# Dart_Controller_SCH.net
KiCad netlist of a schematic drawn in Altium Designer
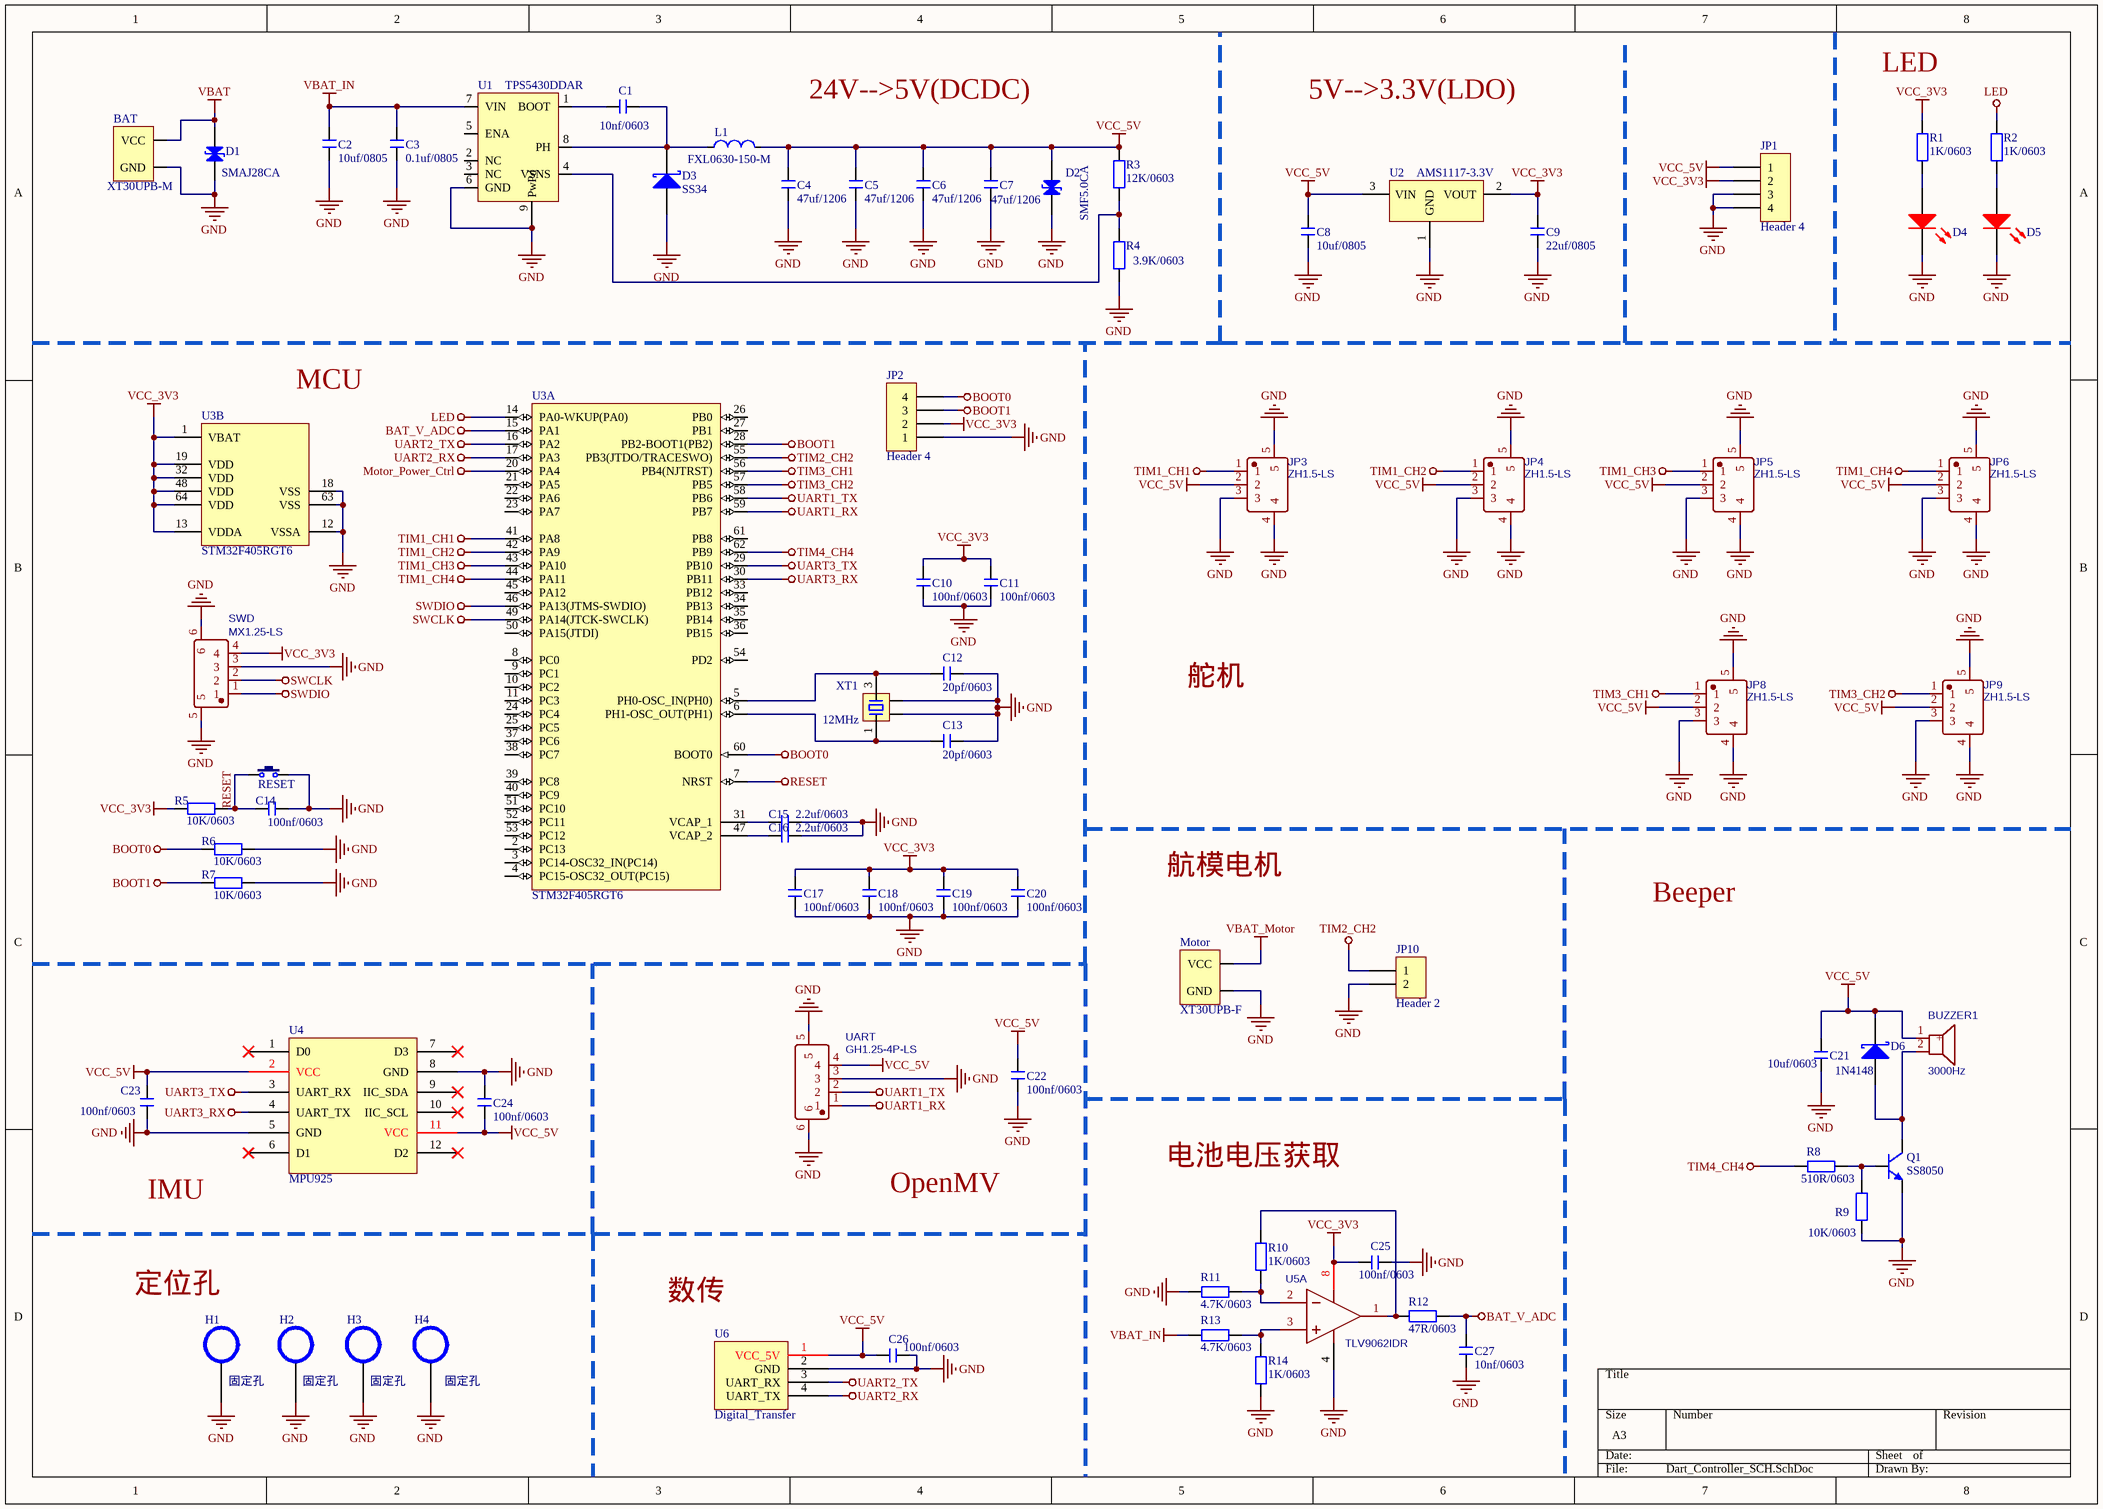
[diagram p0: Dart_Controller_SCH.SchDoc]

(export (version "E")
  (design (tool "Eeschema 10.0.6"))
  (components
    (comp (ref "BAT")
      (value "XT30UPB-M")
      (footprint "XT30UPB-M")
      (description "公头(立式)")
      (libsource (lib "Dart_Controller_Schlib") (part "XT30UPB-M"))
    )
    (comp (ref "BUZZER1")
      (value "3000Hz")
      (footprint "BUZ-TH_BD9.6-P5.00-D0.7-FD")
      (description "蜂鸣器")
      (fields (field (name "MANUFACTURER") "华能") (field (name "MANUFACTURER PART") "HNB09A05"))
      (libsource (lib "Dart_Controller_Schlib") (part "3000Hz"))
    )
    (comp (ref "C1")
      (value "10nf/0603")
      (footprint "C 0603_M")
      (description "贴片电容")
      (libsource (lib "Dart_Controller_Schlib") (part "C 0603"))
    )
    (comp (ref "C2")
      (value "10uf/0805")
      (footprint "C 0805_M")
      (description "贴片电容")
      (libsource (lib "Dart_Controller_Schlib") (part "C 0805"))
    )
    (comp (ref "C3")
      (value "0.1uf/0805")
      (footprint "C 0805_M")
      (description "贴片电容")
      (libsource (lib "Dart_Controller_Schlib") (part "C 0805"))
    )
    (comp (ref "C4")
      (value "47uf/1206")
      (footprint "C 1206_M")
      (description "贴片电容")
      (libsource (lib "Dart_Controller_Schlib") (part "C 1206"))
    )
    (comp (ref "C5")
      (value "47uf/1206")
      (footprint "C 1206_M")
      (description "贴片电容")
      (libsource (lib "Dart_Controller_Schlib") (part "C 1206"))
    )
    (comp (ref "C6")
      (value "47uf/1206")
      (footprint "C 1206_M")
      (description "贴片电容")
      (libsource (lib "Dart_Controller_Schlib") (part "C 1206"))
    )
    (comp (ref "C7")
      (value "47uf/1206")
      (footprint "C 1206_M")
      (description "贴片电容")
      (libsource (lib "Dart_Controller_Schlib") (part "C 1206"))
    )
    (comp (ref "C8")
      (value "10uf/0805")
      (footprint "C 0805_M")
      (description "贴片电容")
      (libsource (lib "Dart_Controller_Schlib") (part "C 0805"))
    )
    (comp (ref "C9")
      (value "22uf/0805")
      (footprint "C 0805_M")
      (description "贴片电容")
      (libsource (lib "Dart_Controller_Schlib") (part "C 0805"))
    )
    (comp (ref "C10")
      (value "100nf/0603")
      (footprint "C 0603_M")
      (description "贴片电容")
      (libsource (lib "Dart_Controller_Schlib") (part "C 0603"))
    )
    (comp (ref "C11")
      (value "100nf/0603")
      (footprint "C 0603_M")
      (description "贴片电容")
      (libsource (lib "Dart_Controller_Schlib") (part "C 0603"))
    )
    (comp (ref "C12")
      (value "20pf/0603")
      (footprint "C 0603_M")
      (description "贴片电容")
      (libsource (lib "Dart_Controller_Schlib") (part "C 0603"))
    )
    (comp (ref "C13")
      (value "20pf/0603")
      (footprint "C 0603_M")
      (description "贴片电容")
      (libsource (lib "Dart_Controller_Schlib") (part "C 0603"))
    )
    (comp (ref "C14")
      (value "100nf/0603")
      (footprint "C 0603_M")
      (description "贴片电容")
      (libsource (lib "Dart_Controller_Schlib") (part "C 0603"))
    )
    (comp (ref "C15")
      (value "2.2uf/0603")
      (footprint "C 0603_M")
      (description "贴片电容")
      (libsource (lib "Dart_Controller_Schlib") (part "C 0603"))
    )
    (comp (ref "C16")
      (value "2.2uf/0603")
      (footprint "C 0603_M")
      (description "贴片电容")
      (libsource (lib "Dart_Controller_Schlib") (part "C 0603"))
    )
    (comp (ref "C17")
      (value "100nf/0603")
      (footprint "C 0603_M")
      (description "贴片电容")
      (libsource (lib "Dart_Controller_Schlib") (part "C 0603"))
    )
    (comp (ref "C18")
      (value "100nf/0603")
      (footprint "C 0603_M")
      (description "贴片电容")
      (libsource (lib "Dart_Controller_Schlib") (part "C 0603"))
    )
    (comp (ref "C19")
      (value "100nf/0603")
      (footprint "C 0603_M")
      (description "贴片电容")
      (libsource (lib "Dart_Controller_Schlib") (part "C 0603"))
    )
    (comp (ref "C20")
      (value "100nf/0603")
      (footprint "C 0603_M")
      (description "贴片电容")
      (libsource (lib "Dart_Controller_Schlib") (part "C 0603"))
    )
    (comp (ref "C21")
      (value "10uf/0603")
      (footprint "C 0603_M")
      (description "贴片电容")
      (libsource (lib "Dart_Controller_Schlib") (part "C 0603"))
    )
    (comp (ref "C22")
      (value "100nf/0603")
      (footprint "C 0603_M")
      (description "贴片电容")
      (libsource (lib "Dart_Controller_Schlib") (part "C 0603"))
    )
    (comp (ref "C23")
      (value "100nf/0603")
      (footprint "C 0603_M")
      (description "贴片电容")
      (libsource (lib "Dart_Controller_Schlib") (part "C 0603"))
    )
    (comp (ref "C24")
      (value "100nf/0603")
      (footprint "C 0603_M")
      (description "贴片电容")
      (libsource (lib "Dart_Controller_Schlib") (part "C 0603"))
    )
    (comp (ref "C25")
      (value "100nf/0603")
      (footprint "C 0603_M")
      (description "贴片电容")
      (libsource (lib "Cap_Mananger_Schlib") (part "C 0603"))
    )
    (comp (ref "C26")
      (value "100nf/0603")
      (footprint "C 0603_M")
      (description "贴片电容")
      (libsource (lib "Dart_Controller_Schlib") (part "C 0603"))
    )
    (comp (ref "C27")
      (value "10nf/0603")
      (footprint "C 0603_M")
      (description "贴片电容")
      (libsource (lib "Cap_Mananger_Schlib") (part "C 0603"))
    )
    (comp (ref "D1")
      (value "SMAJ28CA")
      (footprint "SMA")
      (description "双向瞬态电压抑制二极管")
      (libsource (lib "Dart_Controller_Schlib") (part "SMAJ28CA"))
    )
    (comp (ref "D2")
      (value "SMF5.0CA")
      (footprint "SOD-123FL_L2.8-W1.8-LS3.7-BI")
      (description "双向瞬态电压抑制二极管")
      (libsource (lib "Dart_Controller_Schlib") (part "SMF5.0CA"))
    )
    (comp (ref "D3")
      (value "SS34")
      (footprint "SMA")
      (description "肖特基二极管")
      (libsource (lib "Dart_Controller_Schlib") (part "SS34"))
    )
    (comp (ref "D4")
      (value "LED")
      (footprint "LED0603-RD_RED")
      (description "发光二极管")
      (fields (field (name "PUBLISHER") "Altium Limited"))
      (libsource (lib "Dart_Controller_Schlib") (part "LED_R"))
    )
    (comp (ref "D5")
      (value "LED")
      (footprint "LED0603-RD_RED")
      (description "发光二极管")
      (fields (field (name "PUBLISHER") "Altium Limited"))
      (libsource (lib "Dart_Controller_Schlib") (part "LED_R"))
    )
    (comp (ref "D6")
      (value "1N4148")
      (footprint "SOD-323_L1.8-W1.3-LS2.5-RD")
      (description "开关二极管")
      (libsource (lib "Dart_Controller_Schlib") (part "1N4148WS"))
    )
    (comp (ref "H1") (value "固定孔") (footprint "铜柱孔") (libsource (lib "Dart_Controller_Schlib") (part "铜柱孔")))
    (comp (ref "H2") (value "固定孔") (footprint "铜柱孔") (libsource (lib "Dart_Controller_Schlib") (part "铜柱孔")))
    (comp (ref "H3") (value "固定孔") (footprint "铜柱孔") (libsource (lib "Dart_Controller_Schlib") (part "铜柱孔")))
    (comp (ref "H4") (value "固定孔") (footprint "铜柱孔") (libsource (lib "Dart_Controller_Schlib") (part "铜柱孔")))
    (comp (ref "JP1")
      (value "Header 4")
      (footprint "HDR2.54-LI-4P")
      (description "Header, 4-Pin")
      (fields (field (name "PUBLISHER") "Altium Limited"))
      (libsource (lib "Dart_Controller_Schlib") (part "Header 4"))
    )
    (comp (ref "JP2")
      (value "Header 4")
      (footprint "HDR2.54-LI-4P")
      (description "Header, 4-Pin")
      (fields (field (name "PUBLISHER") "Altium Limited"))
      (libsource (lib "") (part "Header 4_1"))
    )
    (comp (ref "JP3")
      (value "ZH1.5-LS")
      (footprint "ZH1.5")
      (fields
        (field (name "MANUFACTURER") "HCTL(华灿天禄)")
        (field (name "MANUFACTURER PART") "HC-ZH-3PLT")
        (field (name "CONTRIBUTOR") "LCSC")
      )
      (libsource (lib "Dart_Controller_Schlib") (part "ZH1.5-LS"))
    )
    (comp (ref "JP4")
      (value "ZH1.5-LS")
      (footprint "ZH1.5")
      (fields
        (field (name "MANUFACTURER") "HCTL(华灿天禄)")
        (field (name "MANUFACTURER PART") "HC-ZH-3PLT")
        (field (name "CONTRIBUTOR") "LCSC")
      )
      (libsource (lib "Dart_Controller_Schlib") (part "ZH1.5-LS"))
    )
    (comp (ref "JP5")
      (value "ZH1.5-LS")
      (footprint "ZH1.5")
      (fields
        (field (name "MANUFACTURER") "HCTL(华灿天禄)")
        (field (name "MANUFACTURER PART") "HC-ZH-3PLT")
        (field (name "CONTRIBUTOR") "LCSC")
      )
      (libsource (lib "Dart_Controller_Schlib") (part "ZH1.5-LS"))
    )
    (comp (ref "JP6")
      (value "ZH1.5-LS")
      (footprint "ZH1.5")
      (fields
        (field (name "MANUFACTURER") "HCTL(华灿天禄)")
        (field (name "MANUFACTURER PART") "HC-ZH-3PLT")
        (field (name "CONTRIBUTOR") "LCSC")
      )
      (libsource (lib "Dart_Controller_Schlib") (part "ZH1.5-LS"))
    )
    (comp (ref "JP8")
      (value "ZH1.5-LS")
      (footprint "ZH1.5")
      (fields
        (field (name "MANUFACTURER") "HCTL(华灿天禄)")
        (field (name "MANUFACTURER PART") "HC-ZH-3PLT")
        (field (name "CONTRIBUTOR") "LCSC")
      )
      (libsource (lib "Dart_Controller_Schlib") (part "ZH1.5-LS"))
    )
    (comp (ref "JP9")
      (value "ZH1.5-LS")
      (footprint "ZH1.5")
      (fields
        (field (name "MANUFACTURER") "HCTL(华灿天禄)")
        (field (name "MANUFACTURER PART") "HC-ZH-3PLT")
        (field (name "CONTRIBUTOR") "LCSC")
      )
      (libsource (lib "Dart_Controller_Schlib") (part "ZH1.5-LS"))
    )
    (comp (ref "JP10")
      (value "Header 2")
      (footprint "HDR2.54-LI-2P")
      (description "Header, 2-Pin")
      (fields (field (name "PUBLISHER") "Altium Limited"))
      (libsource (lib "Dart_Controller_Schlib") (part "Header 2"))
    )
    (comp (ref "L1")
      (value "FXL0630-150-M")
      (footprint "L-SMD-0630")
      (description "功率电感")
      (libsource (lib "Dart_Controller_Schlib") (part "FXL0630-150-M"))
    )
    (comp (ref "Motor")
      (value "XT30UPB-F")
      (footprint "XT30UPB-F")
      (description "母头(立式)")
      (libsource (lib "Dart_Controller_Schlib") (part "XT30UPB-F"))
    )
    (comp (ref "Q1")
      (value "SS8050")
      (footprint "SOT23-3L")
      (description "高频放大-NPN型")
      (fields (field (name "版权归属") "封装库来自淘宝 ID：黄晶宝石"))
      (libsource (lib "Dart_Controller_Schlib") (part "SS8050-SMD"))
    )
    (comp (ref "R1")
      (value "1K/0603")
      (footprint "R 0603_M")
      (description "贴片电阻")
      (fields (field (name "版权归属") "来自淘宝 ID：黄晶宝石"))
      (libsource (lib "Dart_Controller_Schlib") (part "R 0603"))
    )
    (comp (ref "R2")
      (value "1K/0603")
      (footprint "R 0603_M")
      (description "贴片电阻")
      (fields (field (name "版权归属") "来自淘宝 ID：黄晶宝石"))
      (libsource (lib "Dart_Controller_Schlib") (part "R 0603"))
    )
    (comp (ref "R3")
      (value "12K/0603")
      (footprint "R 0603_M")
      (description "贴片电阻")
      (fields (field (name "版权归属") "来自淘宝 ID：黄晶宝石"))
      (libsource (lib "Dart_Controller_Schlib") (part "R 0603"))
    )
    (comp (ref "R4")
      (value "3.9K/0603")
      (footprint "R 0603_M")
      (description "贴片电阻")
      (fields (field (name "版权归属") "来自淘宝 ID：黄晶宝石"))
      (libsource (lib "Dart_Controller_Schlib") (part "R 0603"))
    )
    (comp (ref "R5")
      (value "10K/0603")
      (footprint "R 0603_M")
      (description "贴片电阻")
      (fields (field (name "版权归属") "来自淘宝 ID：黄晶宝石"))
      (libsource (lib "Dart_Controller_Schlib") (part "R 0603"))
    )
    (comp (ref "R6")
      (value "10K/0603")
      (footprint "R 0603_M")
      (description "贴片电阻")
      (fields (field (name "版权归属") "来自淘宝 ID：黄晶宝石"))
      (libsource (lib "Dart_Controller_Schlib") (part "R 0603"))
    )
    (comp (ref "R7")
      (value "10K/0603")
      (footprint "R 0603_M")
      (description "贴片电阻")
      (fields (field (name "版权归属") "来自淘宝 ID：黄晶宝石"))
      (libsource (lib "Dart_Controller_Schlib") (part "R 0603"))
    )
    (comp (ref "R8")
      (value "510R/0603")
      (footprint "R 0603_M")
      (description "贴片电阻")
      (fields (field (name "版权归属") "来自淘宝 ID：黄晶宝石"))
      (libsource (lib "Cap_Mananger_Schlib") (part "R 0603"))
    )
    (comp (ref "R9")
      (value "10K/0603")
      (footprint "R 0603_M")
      (description "贴片电阻")
      (fields (field (name "版权归属") "来自淘宝 ID：黄晶宝石"))
      (libsource (lib "Cap_Mananger_Schlib") (part "R 0603"))
    )
    (comp (ref "R10")
      (value "1K/0603")
      (footprint "R 0603_M")
      (description "贴片电阻")
      (fields (field (name "版权归属") "来自淘宝 ID：黄晶宝石"))
      (libsource (lib "Cap_Mananger_Schlib") (part "R 0603"))
    )
    (comp (ref "R11")
      (value "4.7K/0603")
      (footprint "R 0603_M")
      (description "贴片电阻")
      (fields (field (name "版权归属") "来自淘宝 ID：黄晶宝石"))
      (libsource (lib "Cap_Mananger_Schlib") (part "R 0603"))
    )
    (comp (ref "R12")
      (value "47R/0603")
      (footprint "R 0603_M")
      (description "贴片电阻")
      (fields (field (name "版权归属") "来自淘宝 ID：黄晶宝石"))
      (libsource (lib "Cap_Mananger_Schlib") (part "R 0603"))
    )
    (comp (ref "R13")
      (value "4.7K/0603")
      (footprint "R 0603_M")
      (description "贴片电阻")
      (fields (field (name "版权归属") "来自淘宝 ID：黄晶宝石"))
      (libsource (lib "Cap_Mananger_Schlib") (part "R 0603"))
    )
    (comp (ref "R14")
      (value "1K/0603")
      (footprint "R 0603_M")
      (description "贴片电阻")
      (fields (field (name "版权归属") "来自淘宝 ID：黄晶宝石"))
      (libsource (lib "Cap_Mananger_Schlib") (part "R 0603"))
    )
    (comp (ref "RESET")
      (value "3x6x5")
      (footprint "TSW SMD-3*6*2.5")
      (description "3x6轻触开关")
      (fields (field (name "版权归属") "封装库来自淘宝 ID：黄晶宝石"))
      (libsource (lib "Dart_Controller_Schlib") (part "TSW 3x6"))
    )
    (comp (ref "SWD")
      (value "MX1.25-LS")
      (footprint "MX 1.25-LS-4P")
      (fields
        (field (name "MANUFACTURER") "HCTL(华灿天禄)")
        (field (name "MANUFACTURER PART") "HC-1.25-4PLT")
        (field (name "CONTRIBUTOR") "LCSC")
      )
      (libsource (lib "Dart_Controller_Schlib") (part "MX1.25-LS"))
    )
    (comp (ref "U1")
      (value "TPS5430DDAR")
      (footprint "ESOP8")
      (description "降压芯片")
      (libsource (lib "Dart_Controller_Schlib") (part "TPS5430DDAR"))
    )
    (comp (ref "U2")
      (value "AMS1117-3.3V")
      (footprint "SOT-89")
      (description "LDO")
      (libsource (lib "Dart_Controller_Schlib") (part "AMS1117-3.3V(SOT-89)"))
    )
    (comp (ref "U3")
      (value "STM32F405RGT6")
      (footprint "LQFP64 10x10_N")
      (fields (field (name "MANUFACTURER") "STMicroelectronics"))
      (libsource (lib "Dart_Controller_Schlib") (part "STM32F405RGT6"))
    )
    (comp (ref "U4")
      (value "MPU925")
      (footprint "JY901B_MPU9250")
      (libsource (lib "Dart_Controller_Schlib") (part "IMU"))
    )
    (comp (ref "U5")
      (value "TLV9062IDR")
      (footprint "SOP8_N")
      (description "运算放大器")
      (fields
        (field (name "MANUFACTURER") "TI(德州仪器)")
        (field (name "MANUFACTURER PART") "OPA365AIDBVR")
        (field (name "CONTRIBUTOR") "LCSC")
      )
      (libsource (lib "Scap_Schlib_v3.3") (part "TLV9062IDR"))
    )
    (comp (ref "U6")
      (value "Digital_Transfer")
      (footprint "Digital_Transfer")
      (description "数传")
      (libsource (lib "Dart_Controller_Schlib") (part "Digital_Transfer"))
    )
    (comp (ref "UART")
      (value "GH1.25-4P-LS")
      (footprint "GH1.25-LS-4P")
      (fields
        (field (name "MANUFACTURER") "XUNPU(讯普)")
        (field (name "MANUFACTURER PART") "WAFER-GH1.25-4PLB")
        (field (name "CONTRIBUTOR") "lcsc")
      )
      (libsource (lib "Dart_Controller_Schlib") (part "GH1.25-4P-LS"))
    )
    (comp (ref "XT1")
      (value "12MHz")
      (footprint "XTAL_3225_4P")
      (description "无源晶振/外接20pf负载电容")
      (libsource (lib "Dart_Controller_Schlib") (part "X322512MSB4SI"))
    )
  )
  (nets
    (net (code "1") (name "BAT_V_ADC") (class "Default")
      (node (ref "C27") (pin "2") (pinfunction "2_2") (pintype "passive"))
      (node (ref "R12") (pin "2") (pinfunction "2_2") (pintype "passive"))
      (node (ref "U3") (pin "15") (pinfunction "PA1_15") (pintype "bidirectional"))
    )
    (net (code "2") (name "BOOT0") (class "Default")
      (node (ref "JP2") (pin "4") (pinfunction "4_4") (pintype "passive"))
      (node (ref "R6") (pin "2") (pinfunction "2_2") (pintype "passive"))
      (node (ref "U3") (pin "60") (pinfunction "BOOT0_60") (pintype "input"))
    )
    (net (code "3") (name "BOOT1") (class "Default")
      (node (ref "JP2") (pin "3") (pinfunction "3_3") (pintype "passive"))
      (node (ref "R7") (pin "2") (pinfunction "2_2") (pintype "passive"))
      (node (ref "U3") (pin "28") (pinfunction "PB2-BOOT1(PB2)_28") (pintype "bidirectional"))
    )
    (net (code "4") (name "GND") (class "Default")
      (node (ref "BAT") (pin "2") (pinfunction "GND_2") (pintype "passive"))
      (node (ref "C10") (pin "1") (pinfunction "1_1") (pintype "passive"))
      (node (ref "C11") (pin "1") (pinfunction "1_1") (pintype "passive"))
      (node (ref "C12") (pin "2") (pinfunction "2_2") (pintype "passive"))
      (node (ref "C13") (pin "2") (pinfunction "2_2") (pintype "passive"))
      (node (ref "C14") (pin "1") (pinfunction "1_1") (pintype "passive"))
      (node (ref "C15") (pin "2") (pinfunction "2_2") (pintype "passive"))
      (node (ref "C16") (pin "2") (pinfunction "2_2") (pintype "passive"))
      (node (ref "C17") (pin "1") (pinfunction "1_1") (pintype "passive"))
      (node (ref "C18") (pin "1") (pinfunction "1_1") (pintype "passive"))
      (node (ref "C19") (pin "1") (pinfunction "1_1") (pintype "passive"))
      (node (ref "C2") (pin "1") (pinfunction "1_1") (pintype "passive"))
      (node (ref "C20") (pin "1") (pinfunction "1_1") (pintype "passive"))
      (node (ref "C21") (pin "2") (pinfunction "2_2") (pintype "passive"))
      (node (ref "C22") (pin "2") (pinfunction "2_2") (pintype "passive"))
      (node (ref "C23") (pin "1") (pinfunction "1_1") (pintype "passive"))
      (node (ref "C24") (pin "2") (pinfunction "2_2") (pintype "passive"))
      (node (ref "C25") (pin "1") (pinfunction "1_1") (pintype "passive"))
      (node (ref "C26") (pin "2") (pinfunction "2_2") (pintype "passive"))
      (node (ref "C27") (pin "1") (pinfunction "1_1") (pintype "passive"))
      (node (ref "C3") (pin "1") (pinfunction "1_1") (pintype "passive"))
      (node (ref "C4") (pin "1") (pinfunction "1_1") (pintype "passive"))
      (node (ref "C5") (pin "1") (pinfunction "1_1") (pintype "passive"))
      (node (ref "C6") (pin "1") (pinfunction "1_1") (pintype "passive"))
      (node (ref "C7") (pin "1") (pinfunction "1_1") (pintype "passive"))
      (node (ref "C8") (pin "1") (pinfunction "1_1") (pintype "passive"))
      (node (ref "C9") (pin "1") (pinfunction "1_1") (pintype "passive"))
      (node (ref "D1") (pin "2") (pinfunction "2_2") (pintype "passive"))
      (node (ref "D2") (pin "2") (pinfunction "2_2") (pintype "passive"))
      (node (ref "D3") (pin "1") (pinfunction "A_1") (pintype "passive"))
      (node (ref "D4") (pin "1") (pinfunction "K_1") (pintype "passive"))
      (node (ref "D5") (pin "1") (pinfunction "K_1") (pintype "passive"))
      (node (ref "H1") (pin "1") (pinfunction "11_1") (pintype "passive"))
      (node (ref "H2") (pin "1") (pinfunction "11_1") (pintype "passive"))
      (node (ref "H3") (pin "1") (pinfunction "11_1") (pintype "passive"))
      (node (ref "H4") (pin "1") (pinfunction "11_1") (pintype "passive"))
      (node (ref "JP1") (pin "3") (pinfunction "3_3") (pintype "passive"))
      (node (ref "JP1") (pin "4") (pinfunction "4_4") (pintype "passive"))
      (node (ref "JP10") (pin "2") (pinfunction "2_2") (pintype "passive"))
      (node (ref "JP2") (pin "1") (pinfunction "1_1") (pintype "passive"))
      (node (ref "JP3") (pin "3") (pinfunction "3_3") (pintype "passive"))
      (node (ref "JP3") (pin "4") (pinfunction "4_4") (pintype "passive"))
      (node (ref "JP3") (pin "5") (pinfunction "5_5") (pintype "passive"))
      (node (ref "JP4") (pin "3") (pinfunction "3_3") (pintype "passive"))
      (node (ref "JP4") (pin "4") (pinfunction "4_4") (pintype "passive"))
      (node (ref "JP4") (pin "5") (pinfunction "5_5") (pintype "passive"))
      (node (ref "JP5") (pin "3") (pinfunction "3_3") (pintype "passive"))
      (node (ref "JP5") (pin "4") (pinfunction "4_4") (pintype "passive"))
      (node (ref "JP5") (pin "5") (pinfunction "5_5") (pintype "passive"))
      (node (ref "JP6") (pin "3") (pinfunction "3_3") (pintype "passive"))
      (node (ref "JP6") (pin "4") (pinfunction "4_4") (pintype "passive"))
      (node (ref "JP6") (pin "5") (pinfunction "5_5") (pintype "passive"))
      (node (ref "JP8") (pin "3") (pinfunction "3_3") (pintype "passive"))
      (node (ref "JP8") (pin "4") (pinfunction "4_4") (pintype "passive"))
      (node (ref "JP8") (pin "5") (pinfunction "5_5") (pintype "passive"))
      (node (ref "JP9") (pin "3") (pinfunction "3_3") (pintype "passive"))
      (node (ref "JP9") (pin "4") (pinfunction "4_4") (pintype "passive"))
      (node (ref "JP9") (pin "5") (pinfunction "5_5") (pintype "passive"))
      (node (ref "Motor") (pin "2") (pinfunction "GND_2") (pintype "passive"))
      (node (ref "Q1") (pin "2") (pinfunction "E_2") (pintype "passive"))
      (node (ref "R11") (pin "1") (pinfunction "1_1") (pintype "passive"))
      (node (ref "R14") (pin "1") (pinfunction "1_1") (pintype "passive"))
      (node (ref "R4") (pin "1") (pinfunction "1_1") (pintype "passive"))
      (node (ref "R6") (pin "1") (pinfunction "1_1") (pintype "passive"))
      (node (ref "R7") (pin "1") (pinfunction "1_1") (pintype "passive"))
      (node (ref "R9") (pin "1") (pinfunction "1_1") (pintype "passive"))
      (node (ref "RESET") (pin "2") (pinfunction "2_2") (pintype "passive"))
      (node (ref "SWD") (pin "3") (pinfunction "3_3") (pintype "passive"))
      (node (ref "SWD") (pin "5") (pinfunction "5_5") (pintype "passive"))
      (node (ref "SWD") (pin "6") (pinfunction "6_6") (pintype "passive"))
      (node (ref "U1") (pin "6") (pinfunction "GND_6") (pintype "passive"))
      (node (ref "U1") (pin "9") (pinfunction "PwPd_9") (pintype "passive"))
      (node (ref "U2") (pin "1") (pinfunction "GND_1") (pintype "passive"))
      (node (ref "U3") (pin "12") (pinfunction "VSSA_12") (pintype "power_in"))
      (node (ref "U3") (pin "18") (pinfunction "VSS_18") (pintype "power_in"))
      (node (ref "U3") (pin "63") (pinfunction "VSS_63") (pintype "power_in"))
      (node (ref "U4") (pin "5") (pinfunction "GND_5") (pintype "passive"))
      (node (ref "U4") (pin "8") (pinfunction "GND_8") (pintype "passive"))
      (node (ref "U5") (pin "4") (pinfunction "VS-_4") (pintype "passive"))
      (node (ref "U6") (pin "2") (pinfunction "GND_2") (pintype "passive"))
      (node (ref "UART") (pin "3") (pinfunction "3_3") (pintype "passive"))
      (node (ref "UART") (pin "5") (pinfunction "5_5") (pintype "passive"))
      (node (ref "UART") (pin "6") (pinfunction "6_6") (pintype "passive"))
      (node (ref "XT1") (pin "2") (pinfunction "2_2") (pintype "passive"))
      (node (ref "XT1") (pin "4") (pinfunction "4_4") (pintype "passive"))
    )
    (net (code "5") (name "LED") (class "Default")
      (node (ref "R2") (pin "2") (pinfunction "2_2") (pintype "passive"))
      (node (ref "U3") (pin "14") (pinfunction "PA0-WKUP(PA0)_14") (pintype "bidirectional"))
    )
    (net (code "6") (name "Motor_Power_Ctrl") (class "Default")
      (node (ref "U3") (pin "20") (pinfunction "PA4_20") (pintype "bidirectional"))
    )
    (net (code "7") (name "Net-(D3-K)") (class "Default")
      (node (ref "C1") (pin "1") (pinfunction "1_1") (pintype "passive"))
      (node (ref "D3") (pin "2") (pinfunction "K_2") (pintype "passive"))
      (node (ref "L1") (pin "1") (pinfunction "1_1") (pintype "passive"))
      (node (ref "U1") (pin "8") (pinfunction "PH_8") (pintype "passive"))
    )
    (net (code "8") (name "Net-(D4-A)") (class "Default")
      (node (ref "D4") (pin "2") (pinfunction "A_2") (pintype "passive"))
      (node (ref "R1") (pin "1") (pinfunction "1_1") (pintype "passive"))
    )
    (net (code "9") (name "Net-(D5-A)") (class "Default")
      (node (ref "D5") (pin "2") (pinfunction "A_2") (pintype "passive"))
      (node (ref "R2") (pin "1") (pinfunction "1_1") (pintype "passive"))
    )
    (net (code "10") (name "Net-(D6-A)") (class "Default")
      (node (ref "BUZZER1") (pin "2") (pinfunction "2_2") (pintype "passive"))
      (node (ref "D6") (pin "1") (pinfunction "A_1") (pintype "passive"))
      (node (ref "Q1") (pin "3") (pinfunction "C_3") (pintype "passive"))
    )
    (net (code "11") (name "Net-(Q1-B)") (class "Default")
      (node (ref "Q1") (pin "1") (pinfunction "B_1") (pintype "passive"))
      (node (ref "R8") (pin "2") (pinfunction "2_2") (pintype "passive"))
      (node (ref "R9") (pin "2") (pinfunction "2_2") (pintype "passive"))
    )
    (net (code "12") (name "Net-(U1-BOOT)") (class "Default")
      (node (ref "C1") (pin "2") (pinfunction "2_2") (pintype "passive"))
      (node (ref "U1") (pin "1") (pinfunction "BOOT_1") (pintype "passive"))
    )
    (net (code "13") (name "Net-(U1-VSNS)") (class "Default")
      (node (ref "R3") (pin "1") (pinfunction "1_1") (pintype "passive"))
      (node (ref "R4") (pin "2") (pinfunction "2_2") (pintype "passive"))
      (node (ref "U1") (pin "4") (pinfunction "VSNS_4") (pintype "passive"))
    )
    (net (code "14") (name "Net-(U3A-PH0-OSC_IN(PH0))") (class "Default")
      (node (ref "C12") (pin "1") (pinfunction "1_1") (pintype "passive"))
      (node (ref "U3") (pin "5") (pinfunction "PH0-OSC_IN(PH0)_5") (pintype "bidirectional"))
      (node (ref "XT1") (pin "3") (pinfunction "3_3") (pintype "passive"))
    )
    (net (code "15") (name "Net-(U3A-PH1-OSC_OUT(PH1))") (class "Default")
      (node (ref "C13") (pin "1") (pinfunction "1_1") (pintype "passive"))
      (node (ref "U3") (pin "6") (pinfunction "PH1-OSC_OUT(PH1)_6") (pintype "bidirectional"))
      (node (ref "XT1") (pin "1") (pinfunction "1_1") (pintype "passive"))
    )
    (net (code "16") (name "Net-(U3A-VCAP_1)") (class "Default")
      (node (ref "C15") (pin "1") (pinfunction "1_1") (pintype "passive"))
      (node (ref "U3") (pin "31") (pinfunction "VCAP_1_31") (pintype "power_in"))
    )
    (net (code "17") (name "Net-(U3A-VCAP_2)") (class "Default")
      (node (ref "C16") (pin "1") (pinfunction "1_1") (pintype "passive"))
      (node (ref "U3") (pin "47") (pinfunction "VCAP_2_47") (pintype "power_in"))
    )
    (net (code "18") (name "Net-(U5A-IN+)") (class "Default")
      (node (ref "R13") (pin "2") (pinfunction "2_2") (pintype "passive"))
      (node (ref "R14") (pin "2") (pinfunction "2_2") (pintype "passive"))
      (node (ref "U5") (pin "3") (pinfunction "IN+_3") (pintype "passive"))
    )
    (net (code "19") (name "Net-(U5A-IN-)") (class "Default")
      (node (ref "R10") (pin "1") (pinfunction "1_1") (pintype "passive"))
      (node (ref "R11") (pin "2") (pinfunction "2_2") (pintype "passive"))
      (node (ref "U5") (pin "2") (pinfunction "IN-_2") (pintype "passive"))
    )
    (net (code "20") (name "Net-(U5A-OUT)") (class "Default")
      (node (ref "R10") (pin "2") (pinfunction "2_2") (pintype "passive"))
      (node (ref "R12") (pin "1") (pinfunction "1_1") (pintype "passive"))
      (node (ref "U5") (pin "1") (pinfunction "OUT_1") (pintype "passive"))
    )
    (net (code "21") (name "RESET") (class "Default")
      (node (ref "C14") (pin "2") (pinfunction "2_2") (pintype "passive"))
      (node (ref "R5") (pin "1") (pinfunction "1_1") (pintype "passive"))
      (node (ref "RESET") (pin "1") (pinfunction "1_1") (pintype "passive"))
      (node (ref "U3") (pin "7") (pinfunction "NRST_7") (pintype "bidirectional"))
    )
    (net (code "22") (name "SWCLK") (class "Default")
      (node (ref "SWD") (pin "2") (pinfunction "2_2") (pintype "passive"))
      (node (ref "U3") (pin "49") (pinfunction "PA14(JTCK-SWCLK)_49") (pintype "bidirectional"))
    )
    (net (code "23") (name "SWDIO") (class "Default")
      (node (ref "SWD") (pin "1") (pinfunction "1_1") (pintype "passive"))
      (node (ref "U3") (pin "46") (pinfunction "PA13(JTMS-SWDIO)_46") (pintype "bidirectional"))
    )
    (net (code "24") (name "TIM1_CH1") (class "Default")
      (node (ref "JP3") (pin "1") (pinfunction "1_1") (pintype "passive"))
      (node (ref "U3") (pin "41") (pinfunction "PA8_41") (pintype "bidirectional"))
    )
    (net (code "25") (name "TIM1_CH2") (class "Default")
      (node (ref "JP4") (pin "1") (pinfunction "1_1") (pintype "passive"))
      (node (ref "U3") (pin "42") (pinfunction "PA9_42") (pintype "bidirectional"))
    )
    (net (code "26") (name "TIM1_CH3") (class "Default")
      (node (ref "JP5") (pin "1") (pinfunction "1_1") (pintype "passive"))
      (node (ref "U3") (pin "43") (pinfunction "PA10_43") (pintype "bidirectional"))
    )
    (net (code "27") (name "TIM1_CH4") (class "Default")
      (node (ref "JP6") (pin "1") (pinfunction "1_1") (pintype "passive"))
      (node (ref "U3") (pin "44") (pinfunction "PA11_44") (pintype "bidirectional"))
    )
    (net (code "28") (name "TIM2_CH2") (class "Default")
      (node (ref "JP10") (pin "1") (pinfunction "1_1") (pintype "passive"))
      (node (ref "U3") (pin "55") (pinfunction "PB3(JTDO/TRACESWO)_55") (pintype "bidirectional"))
    )
    (net (code "29") (name "TIM3_CH1") (class "Default")
      (node (ref "JP8") (pin "1") (pinfunction "1_1") (pintype "passive"))
      (node (ref "U3") (pin "56") (pinfunction "PB4(NJTRST)_56") (pintype "bidirectional"))
    )
    (net (code "30") (name "TIM3_CH2") (class "Default")
      (node (ref "JP9") (pin "1") (pinfunction "1_1") (pintype "passive"))
      (node (ref "U3") (pin "57") (pinfunction "PB5_57") (pintype "bidirectional"))
    )
    (net (code "31") (name "TIM4_CH4") (class "Default")
      (node (ref "R8") (pin "1") (pinfunction "1_1") (pintype "passive"))
      (node (ref "U3") (pin "62") (pinfunction "PB9_62") (pintype "bidirectional"))
    )
    (net (code "32") (name "UART1_RX") (class "Default")
      (node (ref "U3") (pin "59") (pinfunction "PB7_59") (pintype "bidirectional"))
      (node (ref "UART") (pin "1") (pinfunction "1_1") (pintype "passive"))
    )
    (net (code "33") (name "UART1_TX") (class "Default")
      (node (ref "U3") (pin "58") (pinfunction "PB6_58") (pintype "bidirectional"))
      (node (ref "UART") (pin "2") (pinfunction "2_2") (pintype "passive"))
    )
    (net (code "34") (name "UART2_RX") (class "Default")
      (node (ref "U3") (pin "17") (pinfunction "PA3_17") (pintype "bidirectional"))
      (node (ref "U6") (pin "4") (pinfunction "UART_TX_4") (pintype "passive"))
    )
    (net (code "35") (name "UART2_TX") (class "Default")
      (node (ref "U3") (pin "16") (pinfunction "PA2_16") (pintype "bidirectional"))
      (node (ref "U6") (pin "3") (pinfunction "UART_RX_3") (pintype "passive"))
    )
    (net (code "36") (name "UART3_RX") (class "Default")
      (node (ref "U3") (pin "30") (pinfunction "PB11_30") (pintype "bidirectional"))
      (node (ref "U4") (pin "4") (pinfunction "UART_TX_4") (pintype "passive"))
    )
    (net (code "37") (name "UART3_TX") (class "Default")
      (node (ref "U3") (pin "29") (pinfunction "PB10_29") (pintype "bidirectional"))
      (node (ref "U4") (pin "3") (pinfunction "UART_RX_3") (pintype "passive"))
    )
    (net (code "38") (name "VBAT") (class "Default")
      (node (ref "BAT") (pin "1") (pinfunction "VCC_1") (pintype "passive"))
      (node (ref "D1") (pin "1") (pinfunction "1_1") (pintype "passive"))
    )
    (net (code "39") (name "VBAT_IN") (class "Default")
      (node (ref "C2") (pin "2") (pinfunction "2_2") (pintype "passive"))
      (node (ref "C3") (pin "2") (pinfunction "2_2") (pintype "passive"))
      (node (ref "R13") (pin "1") (pinfunction "1_1") (pintype "passive"))
      (node (ref "U1") (pin "7") (pinfunction "VIN_7") (pintype "passive"))
    )
    (net (code "40") (name "VBAT_Motor") (class "Default")
      (node (ref "Motor") (pin "1") (pinfunction "VCC_1") (pintype "passive"))
    )
    (net (code "41") (name "VCC_3V3") (class "Default")
      (node (ref "C10") (pin "2") (pinfunction "2_2") (pintype "passive"))
      (node (ref "C11") (pin "2") (pinfunction "2_2") (pintype "passive"))
      (node (ref "C17") (pin "2") (pinfunction "2_2") (pintype "passive"))
      (node (ref "C18") (pin "2") (pinfunction "2_2") (pintype "passive"))
      (node (ref "C19") (pin "2") (pinfunction "2_2") (pintype "passive"))
      (node (ref "C20") (pin "2") (pinfunction "2_2") (pintype "passive"))
      (node (ref "C25") (pin "2") (pinfunction "2_2") (pintype "passive"))
      (node (ref "C9") (pin "2") (pinfunction "2_2") (pintype "passive"))
      (node (ref "JP1") (pin "2") (pinfunction "2_2") (pintype "passive"))
      (node (ref "JP2") (pin "2") (pinfunction "2_2") (pintype "passive"))
      (node (ref "R1") (pin "2") (pinfunction "2_2") (pintype "passive"))
      (node (ref "R5") (pin "2") (pinfunction "2_2") (pintype "passive"))
      (node (ref "SWD") (pin "4") (pinfunction "4_4") (pintype "passive"))
      (node (ref "U2") (pin "2") (pinfunction "VOUT_2") (pintype "passive"))
      (node (ref "U3") (pin "1") (pinfunction "VBAT_1") (pintype "power_in"))
      (node (ref "U3") (pin "13") (pinfunction "VDDA_13") (pintype "power_in"))
      (node (ref "U3") (pin "19") (pinfunction "VDD_19") (pintype "power_in"))
      (node (ref "U3") (pin "32") (pinfunction "VDD_32") (pintype "power_in"))
      (node (ref "U3") (pin "48") (pinfunction "VDD_48") (pintype "power_in"))
      (node (ref "U3") (pin "64") (pinfunction "VDD_64") (pintype "power_in"))
      (node (ref "U5") (pin "8") (pinfunction "VS+_8") (pintype "passive"))
    )
    (net (code "42") (name "VCC_5V") (class "Default")
      (node (ref "BUZZER1") (pin "1") (pinfunction "+_1") (pintype "passive"))
      (node (ref "C21") (pin "1") (pinfunction "1_1") (pintype "passive"))
      (node (ref "C22") (pin "1") (pinfunction "1_1") (pintype "passive"))
      (node (ref "C23") (pin "2") (pinfunction "2_2") (pintype "passive"))
      (node (ref "C24") (pin "1") (pinfunction "1_1") (pintype "passive"))
      (node (ref "C26") (pin "1") (pinfunction "1_1") (pintype "passive"))
      (node (ref "C4") (pin "2") (pinfunction "2_2") (pintype "passive"))
      (node (ref "C5") (pin "2") (pinfunction "2_2") (pintype "passive"))
      (node (ref "C6") (pin "2") (pinfunction "2_2") (pintype "passive"))
      (node (ref "C7") (pin "2") (pinfunction "2_2") (pintype "passive"))
      (node (ref "C8") (pin "2") (pinfunction "2_2") (pintype "passive"))
      (node (ref "D2") (pin "1") (pinfunction "1_1") (pintype "passive"))
      (node (ref "D6") (pin "2") (pinfunction "K_2") (pintype "passive"))
      (node (ref "JP1") (pin "1") (pinfunction "1_1") (pintype "passive"))
      (node (ref "JP3") (pin "2") (pinfunction "2_2") (pintype "passive"))
      (node (ref "JP4") (pin "2") (pinfunction "2_2") (pintype "passive"))
      (node (ref "JP5") (pin "2") (pinfunction "2_2") (pintype "passive"))
      (node (ref "JP6") (pin "2") (pinfunction "2_2") (pintype "passive"))
      (node (ref "JP8") (pin "2") (pinfunction "2_2") (pintype "passive"))
      (node (ref "JP9") (pin "2") (pinfunction "2_2") (pintype "passive"))
      (node (ref "L1") (pin "2") (pinfunction "2_2") (pintype "passive"))
      (node (ref "R3") (pin "2") (pinfunction "2_2") (pintype "passive"))
      (node (ref "U2") (pin "3") (pinfunction "VIN_3") (pintype "passive"))
      (node (ref "U4") (pin "11") (pinfunction "VCC_11") (pintype "passive"))
      (node (ref "U4") (pin "2") (pinfunction "VCC_2") (pintype "passive"))
      (node (ref "U6") (pin "1") (pinfunction "VCC_5V_1") (pintype "passive"))
      (node (ref "UART") (pin "4") (pinfunction "4_4") (pintype "passive"))
    )
    (net (code "43") (name "unconnected-(U1-ENA-Pad5)") (class "Default")
      (node (ref "U1") (pin "5") (pinfunction "ENA_5") (pintype "passive"))
    )
    (net (code "44") (name "unconnected-(U1-NC-Pad2)") (class "Default")
      (node (ref "U1") (pin "2") (pinfunction "NC_2") (pintype "passive"))
    )
    (net (code "45") (name "unconnected-(U1-NC-Pad3)") (class "Default")
      (node (ref "U1") (pin "3") (pinfunction "NC_3") (pintype "passive"))
    )
    (net (code "46") (name "unconnected-(U3A-PA5-Pad21)") (class "Default")
      (node (ref "U3") (pin "21") (pinfunction "PA5_21") (pintype "bidirectional"))
    )
    (net (code "47") (name "unconnected-(U3A-PA6-Pad22)") (class "Default")
      (node (ref "U3") (pin "22") (pinfunction "PA6_22") (pintype "bidirectional"))
    )
    (net (code "48") (name "unconnected-(U3A-PA7-Pad23)") (class "Default")
      (node (ref "U3") (pin "23") (pinfunction "PA7_23") (pintype "bidirectional"))
    )
    (net (code "49") (name "unconnected-(U3A-PA12-Pad45)") (class "Default")
      (node (ref "U3") (pin "45") (pinfunction "PA12_45") (pintype "bidirectional"))
    )
    (net (code "50") (name "unconnected-(U3A-PA15(JTDI)-Pad50)") (class "Default")
      (node (ref "U3") (pin "50") (pinfunction "PA15(JTDI)_50") (pintype "bidirectional"))
    )
    (net (code "51") (name "unconnected-(U3A-PB0-Pad26)") (class "Default")
      (node (ref "U3") (pin "26") (pinfunction "PB0_26") (pintype "bidirectional"))
    )
    (net (code "52") (name "unconnected-(U3A-PB1-Pad27)") (class "Default")
      (node (ref "U3") (pin "27") (pinfunction "PB1_27") (pintype "bidirectional"))
    )
    (net (code "53") (name "unconnected-(U3A-PB8-Pad61)") (class "Default")
      (node (ref "U3") (pin "61") (pinfunction "PB8_61") (pintype "bidirectional"))
    )
    (net (code "54") (name "unconnected-(U3A-PB12-Pad33)") (class "Default")
      (node (ref "U3") (pin "33") (pinfunction "PB12_33") (pintype "bidirectional"))
    )
    (net (code "55") (name "unconnected-(U3A-PB13-Pad34)") (class "Default")
      (node (ref "U3") (pin "34") (pinfunction "PB13_34") (pintype "bidirectional"))
    )
    (net (code "56") (name "unconnected-(U3A-PB14-Pad35)") (class "Default")
      (node (ref "U3") (pin "35") (pinfunction "PB14_35") (pintype "bidirectional"))
    )
    (net (code "57") (name "unconnected-(U3A-PB15-Pad36)") (class "Default")
      (node (ref "U3") (pin "36") (pinfunction "PB15_36") (pintype "bidirectional"))
    )
    (net (code "58") (name "unconnected-(U3A-PC0-Pad8)") (class "Default")
      (node (ref "U3") (pin "8") (pinfunction "PC0_8") (pintype "bidirectional"))
    )
    (net (code "59") (name "unconnected-(U3A-PC1-Pad9)") (class "Default")
      (node (ref "U3") (pin "9") (pinfunction "PC1_9") (pintype "bidirectional"))
    )
    (net (code "60") (name "unconnected-(U3A-PC2-Pad10)") (class "Default")
      (node (ref "U3") (pin "10") (pinfunction "PC2_10") (pintype "bidirectional"))
    )
    (net (code "61") (name "unconnected-(U3A-PC3-Pad11)") (class "Default")
      (node (ref "U3") (pin "11") (pinfunction "PC3_11") (pintype "bidirectional"))
    )
    (net (code "62") (name "unconnected-(U3A-PC4-Pad24)") (class "Default")
      (node (ref "U3") (pin "24") (pinfunction "PC4_24") (pintype "bidirectional"))
    )
    (net (code "63") (name "unconnected-(U3A-PC5-Pad25)") (class "Default")
      (node (ref "U3") (pin "25") (pinfunction "PC5_25") (pintype "bidirectional"))
    )
    (net (code "64") (name "unconnected-(U3A-PC6-Pad37)") (class "Default")
      (node (ref "U3") (pin "37") (pinfunction "PC6_37") (pintype "bidirectional"))
    )
    (net (code "65") (name "unconnected-(U3A-PC7-Pad38)") (class "Default")
      (node (ref "U3") (pin "38") (pinfunction "PC7_38") (pintype "bidirectional"))
    )
    (net (code "66") (name "unconnected-(U3A-PC8-Pad39)") (class "Default")
      (node (ref "U3") (pin "39") (pinfunction "PC8_39") (pintype "bidirectional"))
    )
    (net (code "67") (name "unconnected-(U3A-PC9-Pad40)") (class "Default")
      (node (ref "U3") (pin "40") (pinfunction "PC9_40") (pintype "bidirectional"))
    )
    (net (code "68") (name "unconnected-(U3A-PC10-Pad51)") (class "Default")
      (node (ref "U3") (pin "51") (pinfunction "PC10_51") (pintype "bidirectional"))
    )
    (net (code "69") (name "unconnected-(U3A-PC11-Pad52)") (class "Default")
      (node (ref "U3") (pin "52") (pinfunction "PC11_52") (pintype "bidirectional"))
    )
    (net (code "70") (name "unconnected-(U3A-PC12-Pad53)") (class "Default")
      (node (ref "U3") (pin "53") (pinfunction "PC12_53") (pintype "bidirectional"))
    )
    (net (code "71") (name "unconnected-(U3A-PC13-Pad2)") (class "Default")
      (node (ref "U3") (pin "2") (pinfunction "PC13_2") (pintype "bidirectional"))
    )
    (net (code "72") (name "unconnected-(U3A-PC14-OSC32_IN(PC14)-Pad3)") (class "Default")
      (node (ref "U3") (pin "3") (pinfunction "PC14-OSC32_IN(PC14)_3") (pintype "bidirectional"))
    )
    (net (code "73") (name "unconnected-(U3A-PC15-OSC32_OUT(PC15)-Pad4)") (class "Default")
      (node (ref "U3") (pin "4") (pinfunction "PC15-OSC32_OUT(PC15)_4") (pintype "bidirectional"))
    )
    (net (code "74") (name "unconnected-(U3A-PD2-Pad54)") (class "Default")
      (node (ref "U3") (pin "54") (pinfunction "PD2_54") (pintype "bidirectional"))
    )
    (net (code "75") (name "unconnected-(U4-D0-Pad1)") (class "Default")
      (node (ref "U4") (pin "1") (pinfunction "D0_1") (pintype "passive+no_connect"))
    )
    (net (code "76") (name "unconnected-(U4-D1-Pad6)") (class "Default")
      (node (ref "U4") (pin "6") (pinfunction "D1_6") (pintype "passive+no_connect"))
    )
    (net (code "77") (name "unconnected-(U4-D2-Pad12)") (class "Default")
      (node (ref "U4") (pin "12") (pinfunction "D2_12") (pintype "passive+no_connect"))
    )
    (net (code "78") (name "unconnected-(U4-D3-Pad7)") (class "Default")
      (node (ref "U4") (pin "7") (pinfunction "D3_7") (pintype "passive+no_connect"))
    )
    (net (code "79") (name "unconnected-(U4-IIC_SCL-Pad10)") (class "Default")
      (node (ref "U4") (pin "10") (pinfunction "IIC_SCL_10") (pintype "passive+no_connect"))
    )
    (net (code "80") (name "unconnected-(U4-IIC_SDA-Pad9)") (class "Default")
      (node (ref "U4") (pin "9") (pinfunction "IIC_SDA_9") (pintype "passive+no_connect"))
    )
  )
)
